# RTC_ds1307z.net
KiCad netlist of a schematic drawn in Altium Designer
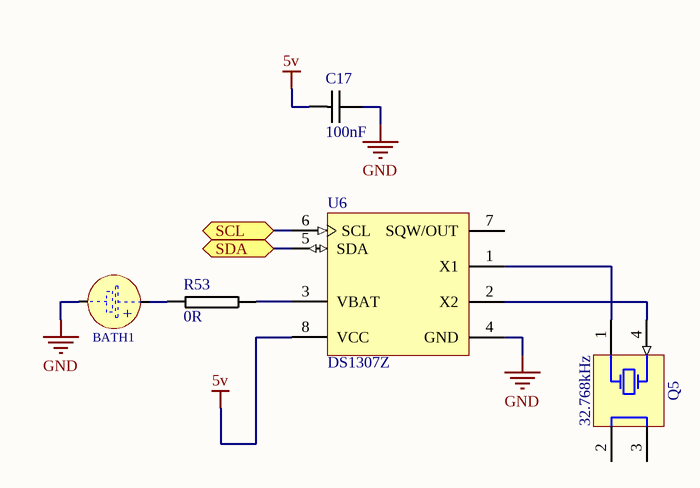
[diagram p0: RTC_ds1307z.SchDoc]

(export (version "E")
  (design (tool "Eeschema 10.0.6"))
  (components
    (comp (ref "BATH1")
      (value "~")
      (footprint "BATH_KEYSTONE_103")
      (description "Battery Holder whit 2 Pin")
      (fields
        (field (name "PART NUMBER") "BATH_KEYSTONE_103")
        (field (name "MANUFACTURER") "KEYSTONE")
        (field (name "AUTHOR") "CERN DEM JLC")
      )
      (libsource (lib "Eletro-mechanical") (part "Battery Holder 2 Pin"))
    )
    (comp (ref "C17")
      (value "100nF")
      (footprint "0805C-TBD")
      (description "CAPACITOR 0805 CERAMIC")
      (libsource (lib "vh_altium_library") (part "0805C-100nF-25V-X7R-MUR"))
    )
    (comp (ref "Q5")
      (value "32.768kHz")
      (footprint "XTAL_EPSON_MC-406")
      (description "Crystal 4 pins 1=XTAL Control 2 And 3=NC 4=XTAL")
      (fields
        (field (name "PART NUMBER") "XTAL_32.768KHZ_EPSON_MC-406 32.768K-A3:ROHS")
        (field (name "MANUFACTURER") "EPSON TOYOCOM")
        (field (name "AUTHOR") "CERN DEM JLC")
      )
      (libsource (lib "ICs And Semiconductors") (part "Quartz Crystal 1X 2-3NC 4X"))
    )
    (comp (ref "R53")
      (value "0R")
      (footprint "0805R-GENERIC")
      (description "RESISTOR 0805 1 WATT")
      (libsource (lib "vh_altium_library") (part "0805R-0R"))
    )
    (comp (ref "U6")
      (value "DS1307Z")
      (footprint "S8-2_N")
      (description "64 x 8, Serial, I2C Real-Time Clock, 5.0V, 8-Pin SO, 0 to 70 degC")
      (libsource (lib "Maxim Real-Time Clocks (RTCs)") (part "DS1307Z"))
    )
  )
  (nets
    (net (code "1") (name "/SCL") (class "Default")
      (node (ref "U6") (pin "6") (pinfunction "SCL_6") (pintype "input"))
    )
    (net (code "2") (name "/SDA") (class "Default")
      (node (ref "U6") (pin "5") (pinfunction "SDA_5") (pintype "bidirectional"))
    )
    (net (code "3") (name "5v") (class "Default")
      (node (ref "C17") (pin "1") (pintype "passive"))
      (node (ref "U6") (pin "8") (pinfunction "VCC_8") (pintype "power_in"))
    )
    (net (code "4") (name "GND") (class "Default")
      (node (ref "BATH1") (pin "2") (pinfunction "MINUS_2") (pintype "power_in"))
      (node (ref "C17") (pin "2") (pintype "passive"))
      (node (ref "U6") (pin "4") (pinfunction "GND_4") (pintype "power_in"))
    )
    (net (code "5") (name "Net-(BATH1-PLUS)") (class "Default")
      (node (ref "BATH1") (pin "1") (pinfunction "PLUS_1") (pintype "power_in"))
      (node (ref "R53") (pin "1") (pintype "passive"))
    )
    (net (code "6") (name "Net-(U6-VBAT)") (class "Default")
      (node (ref "R53") (pin "2") (pintype "passive"))
      (node (ref "U6") (pin "3") (pinfunction "VBAT_3") (pintype "power_in"))
    )
    (net (code "7") (name "Net-(U6-X1)") (class "Default")
      (node (ref "Q5") (pin "1") (pinfunction "X_1") (pintype "power_in"))
      (node (ref "U6") (pin "1") (pinfunction "X1_1") (pintype "passive"))
    )
    (net (code "8") (name "Net-(U6-X2)") (class "Default")
      (node (ref "Q5") (pin "4") (pinfunction "X_4") (pintype "input"))
      (node (ref "U6") (pin "2") (pinfunction "X2_2") (pintype "passive"))
    )
    (net (code "9") (name "unconnected-(Q5-GND-Pad2)") (class "Default")
      (node (ref "Q5") (pin "2") (pinfunction "GND_2") (pintype "power_in"))
    )
    (net (code "10") (name "unconnected-(Q5-GND-Pad3)") (class "Default")
      (node (ref "Q5") (pin "3") (pinfunction "GND_3") (pintype "power_in"))
    )
    (net (code "11") (name "unconnected-(U6-SQW{slash}OUT-Pad7)") (class "Default")
      (node (ref "U6") (pin "7") (pinfunction "SQW/OUT_7") (pintype "open_collector"))
    )
  )
)
